# qi_pad.net
KiCad netlist of a schematic drawn in EAGLE
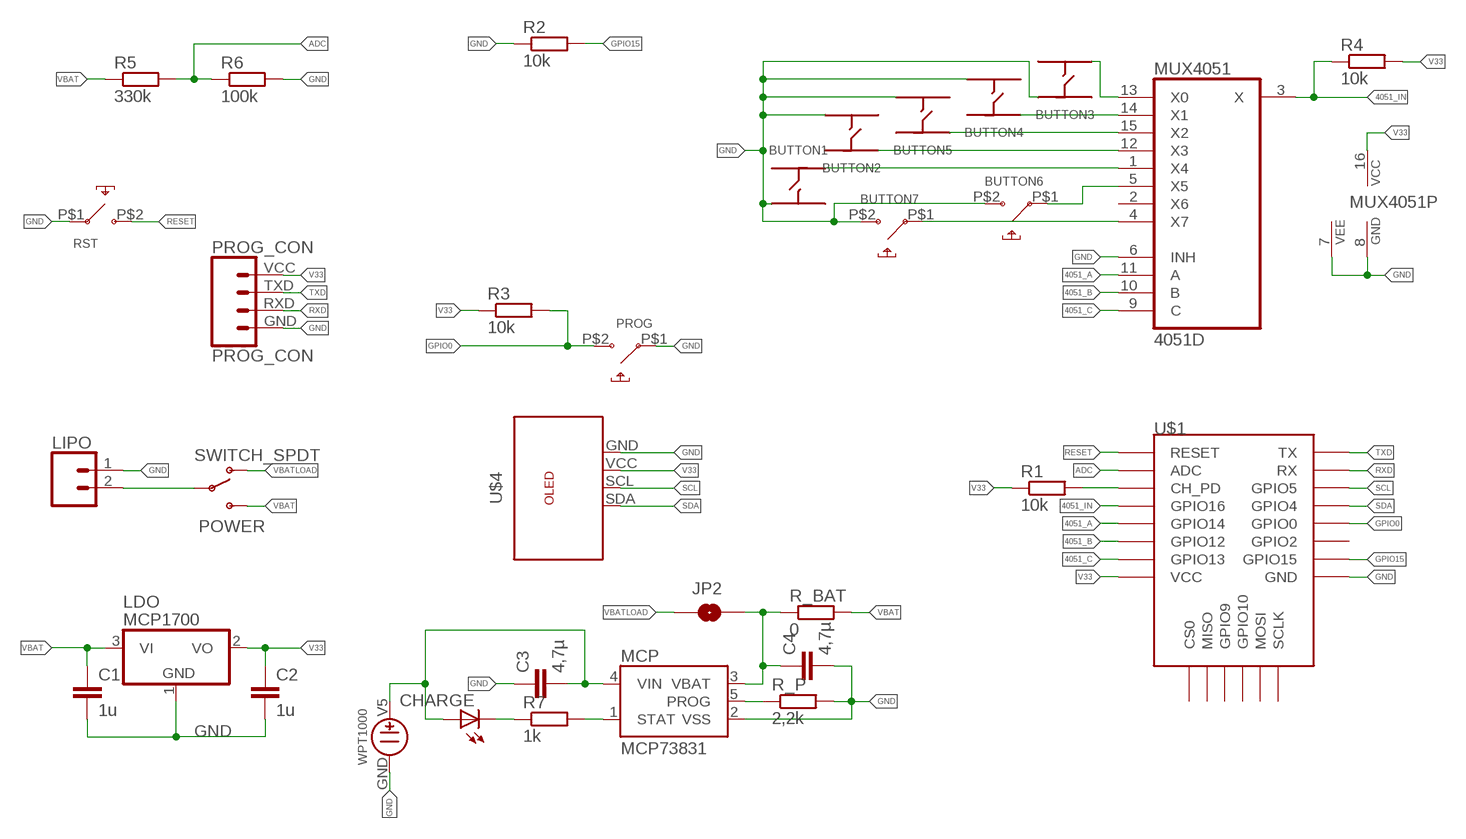
[diagram p0: schematic, sheet 1]

(export (version "E")
  (design (tool "Eeschema 10.0.6"))
  (components
    (comp (ref "BUTTON1")
      (value "6X6BUTTON")
      (footprint "eagle-import:6X6BUTTON")
      (libsource (lib "eagle-import") (part "6X6BUTTON"))
    )
    (comp (ref "BUTTON2")
      (value "6X6BUTTON")
      (footprint "eagle-import:6X6BUTTON")
      (libsource (lib "eagle-import") (part "6X6BUTTON"))
    )
    (comp (ref "BUTTON3")
      (value "6X6BUTTON")
      (footprint "eagle-import:6X6BUTTON")
      (libsource (lib "eagle-import") (part "6X6BUTTON"))
    )
    (comp (ref "BUTTON4")
      (value "6X6BUTTON")
      (footprint "eagle-import:6X6BUTTON")
      (libsource (lib "eagle-import") (part "6X6BUTTON"))
    )
    (comp (ref "BUTTON5")
      (value "6X6BUTTON")
      (footprint "eagle-import:6X6BUTTON")
      (libsource (lib "eagle-import") (part "6X6BUTTON"))
    )
    (comp (ref "BUTTON6")
      (value "3X4_SMD_BUTTON")
      (footprint "eagle-import:3X4BUTTON")
      (libsource (lib "eagle-import") (part "3X4_SMD_BUTTON"))
    )
    (comp (ref "BUTTON7")
      (value "3X4_SMD_BUTTON")
      (footprint "eagle-import:3X4BUTTON")
      (libsource (lib "eagle-import") (part "3X4_SMD_BUTTON"))
    )
    (comp (ref "C1")
      (value "1u")
      (footprint "eagle-import:C1206")
      (libsource (lib "eagle-import") (part "C-EUC1206"))
    )
    (comp (ref "C2")
      (value "1u")
      (footprint "eagle-import:C1206")
      (libsource (lib "eagle-import") (part "C-EUC1206"))
    )
    (comp (ref "C3")
      (value "4,7µ")
      (footprint "eagle-import:C1206")
      (libsource (lib "eagle-import") (part "C-EUC1206"))
    )
    (comp (ref "C4")
      (value "4,7µ")
      (footprint "eagle-import:C1206")
      (libsource (lib "eagle-import") (part "C-EUC1206"))
    )
    (comp (ref "CHARGE")
      (value "LEDCHIPLED_1206")
      (footprint "eagle-import:CHIPLED_1206")
      (libsource (lib "eagle-import") (part "LEDCHIPLED_1206"))
    )
    (comp (ref "JP2")
      (value "JUMPER-SMT_2_NO_NO-SILK")
      (footprint "eagle-import:SMT-JUMPER_2_NO_NO-SILK")
      (libsource (lib "eagle-import") (part "JUMPER-SMT_2_NO_NO-SILK"))
    )
    (comp (ref "LDO")
      (value "MCP1700")
      (footprint "eagle-import:SOT23")
      (libsource (lib "eagle-import") (part "MCP1703CB"))
    )
    (comp (ref "LIPO")
      (value "CONN_02-JST-2MM-SMT")
      (footprint "eagle-import:JST-2-SMD")
      (libsource (lib "eagle-import") (part "CONN_02-JST-2MM-SMT"))
    )
    (comp (ref "MCP")
      (value "MCP73831")
      (footprint "eagle-import:SOT23-5")
      (libsource (lib "eagle-import") (part "MCP73831"))
    )
    (comp (ref "MUX4051")
      (value "4051D")
      (footprint "eagle-import:SO16")
      (libsource (lib "eagle-import") (part "4051D"))
    )
    (comp (ref "POWER")
      (value "SWITCH_SPDT")
      (footprint "eagle-import:KPS-1290")
      (libsource (lib "eagle-import") (part "SWITCH_SPDT"))
    )
    (comp (ref "PROG")
      (value "3X6X3,5BUTTON90")
      (footprint "eagle-import:3X6X3,5BUTTON90")
      (libsource (lib "eagle-import") (part "3X6X3,5BUTTON90"))
    )
    (comp (ref "PROG_CON")
      (value "PROG_CON")
      (footprint "eagle-import:PROG_CON")
      (libsource (lib "eagle-import") (part "PROG_CON"))
    )
    (comp (ref "R1")
      (value "10k")
      (footprint "eagle-import:R0603")
      (libsource (lib "eagle-import") (part "R-EU_R0603"))
    )
    (comp (ref "R2")
      (value "10k")
      (footprint "eagle-import:R0603")
      (libsource (lib "eagle-import") (part "R-EU_R0603"))
    )
    (comp (ref "R3")
      (value "10k")
      (footprint "eagle-import:R0603")
      (libsource (lib "eagle-import") (part "R-EU_R0603"))
    )
    (comp (ref "R4")
      (value "10k")
      (footprint "eagle-import:R0603")
      (libsource (lib "eagle-import") (part "R-EU_R0603"))
    )
    (comp (ref "R5")
      (value "330k")
      (footprint "eagle-import:R0603")
      (libsource (lib "eagle-import") (part "R-EU_R0603"))
    )
    (comp (ref "R6")
      (value "100k")
      (footprint "eagle-import:R0603")
      (libsource (lib "eagle-import") (part "R-EU_R0603"))
    )
    (comp (ref "R7")
      (value "1k")
      (footprint "eagle-import:R0603")
      (libsource (lib "eagle-import") (part "R-EU_R0603"))
    )
    (comp (ref "RST")
      (value "3X6X3,5BUTTON90")
      (footprint "eagle-import:3X6X3,5BUTTON90")
      (libsource (lib "eagle-import") (part "3X6X3,5BUTTON90"))
    )
    (comp (ref "R_BAT")
      (value "0")
      (footprint "eagle-import:R1206")
      (libsource (lib "eagle-import") (part "R-EU_R1206"))
    )
    (comp (ref "R_P")
      (value "2,2k")
      (footprint "eagle-import:R0603")
      (libsource (lib "eagle-import") (part "R-EU_R0603"))
    )
    (comp (ref "U$1")
      (value "ESP8266-12F-SMD")
      (footprint "eagle-import:ESP8266-12F")
      (libsource (lib "eagle-import") (part "ESP8266-12F-SMD"))
    )
    (comp (ref "U$4")
      (value "OLED128X64")
      (footprint "eagle-import:OLED_128X64")
      (libsource (lib "eagle-import") (part "OLED128X64"))
    )
    (comp (ref "WPM1000")
      (value "WPT1000")
      (footprint "eagle-import:WPT1000")
      (libsource (lib "eagle-import") (part "WPT1000"))
    )
  )
  (nets
    (net (code "1") (name "4051_A") (class "Default")
      (node (ref "MUX4051") (pin "11") (pinfunction "A_11") (pintype "input"))
      (node (ref "U$1") (pin "GPIO14") (pinfunction "GPIO14_GPIO14") (pintype "bidirectional"))
    )
    (net (code "2") (name "4051_B") (class "Default")
      (node (ref "MUX4051") (pin "10") (pinfunction "B_10") (pintype "input"))
      (node (ref "U$1") (pin "GPIO12") (pinfunction "GPIO12_GPIO12") (pintype "bidirectional"))
    )
    (net (code "3") (name "4051_C") (class "Default")
      (node (ref "MUX4051") (pin "9") (pinfunction "C_9") (pintype "input"))
      (node (ref "U$1") (pin "GPIO13") (pinfunction "GPIO13_GPIO13") (pintype "bidirectional"))
    )
    (net (code "4") (name "4051_IN") (class "Default")
      (node (ref "MUX4051") (pin "3") (pinfunction "X_3") (pintype "bidirectional"))
      (node (ref "R4") (pin "1") (pinfunction "1_1") (pintype "passive"))
      (node (ref "U$1") (pin "GPIO16") (pinfunction "GPIO16_GPIO16") (pintype "bidirectional"))
    )
    (net (code "5") (name "ADC") (class "Default")
      (node (ref "R5") (pin "2") (pinfunction "2_2") (pintype "passive"))
      (node (ref "R6") (pin "1") (pinfunction "1_1") (pintype "passive"))
      (node (ref "U$1") (pin "ADC") (pinfunction "ADC_ADC") (pintype "bidirectional"))
    )
    (net (code "6") (name "GND") (class "Default")
      (node (ref "BUTTON1") (pin "P1") (pinfunction "A1_P1") (pintype "bidirectional"))
      (node (ref "BUTTON2") (pin "P2") (pinfunction "A2_P2") (pintype "bidirectional"))
      (node (ref "BUTTON3") (pin "P4") (pinfunction "U2_P4") (pintype "bidirectional"))
      (node (ref "BUTTON4") (pin "P2") (pinfunction "A2_P2") (pintype "bidirectional"))
      (node (ref "BUTTON5") (pin "P2") (pinfunction "A2_P2") (pintype "bidirectional"))
      (node (ref "BUTTON6") (pin "P$2") (pinfunction "P2_P$2") (pintype "bidirectional"))
      (node (ref "BUTTON7") (pin "P$2") (pinfunction "P2_P$2") (pintype "bidirectional"))
      (node (ref "C1") (pin "2") (pinfunction "2_2") (pintype "passive"))
      (node (ref "C2") (pin "2") (pinfunction "2_2") (pintype "passive"))
      (node (ref "C3") (pin "1") (pinfunction "1_1") (pintype "passive"))
      (node (ref "C4") (pin "2") (pinfunction "2_2") (pintype "passive"))
      (node (ref "LDO") (pin "1") (pinfunction "GND_1") (pintype "passive"))
      (node (ref "LIPO") (pin "1") (pinfunction "2_1") (pintype "passive"))
      (node (ref "MCP") (pin "2") (pinfunction "VSS_2") (pintype "power_in"))
      (node (ref "MUX4051") (pin "6") (pinfunction "INH_6") (pintype "input"))
      (node (ref "MUX4051") (pin "7") (pinfunction "VEE_7") (pintype "power_in"))
      (node (ref "MUX4051") (pin "8") (pinfunction "GND_8") (pintype "power_in"))
      (node (ref "PROG") (pin "P$1") (pinfunction "P1_P$1") (pintype "bidirectional"))
      (node (ref "PROG_CON") (pin "GND") (pinfunction "1_GND") (pintype "passive"))
      (node (ref "R2") (pin "1") (pinfunction "1_1") (pintype "passive"))
      (node (ref "R6") (pin "2") (pinfunction "2_2") (pintype "passive"))
      (node (ref "RST") (pin "P$1") (pinfunction "P1_P$1") (pintype "bidirectional"))
      (node (ref "R_P") (pin "2") (pinfunction "2_2") (pintype "passive"))
      (node (ref "U$1") (pin "GND") (pinfunction "GND_GND") (pintype "bidirectional"))
      (node (ref "U$4") (pin "GND") (pinfunction "GND_GND") (pintype "bidirectional"))
      (node (ref "WPM1000") (pin "GND") (pinfunction "GND_GND") (pintype "bidirectional"))
    )
    (net (code "7") (name "GPIO0") (class "Default")
      (node (ref "PROG") (pin "P$2") (pinfunction "P2_P$2") (pintype "bidirectional"))
      (node (ref "R3") (pin "2") (pinfunction "2_2") (pintype "passive"))
      (node (ref "U$1") (pin "GPIO0") (pinfunction "GPIO0_GPIO0") (pintype "bidirectional"))
    )
    (net (code "8") (name "GPIO15") (class "Default")
      (node (ref "R2") (pin "2") (pinfunction "2_2") (pintype "passive"))
      (node (ref "U$1") (pin "GPIO15") (pinfunction "GPIO15_GPIO15") (pintype "bidirectional"))
    )
    (net (code "9") (name "Net-(BUTTON1-U2)") (class "Default")
      (node (ref "BUTTON1") (pin "P4") (pinfunction "U2_P4") (pintype "bidirectional"))
      (node (ref "MUX4051") (pin "1") (pinfunction "X4_1") (pintype "bidirectional"))
    )
    (net (code "10") (name "Net-(BUTTON2-U1)") (class "Default")
      (node (ref "BUTTON2") (pin "P3") (pinfunction "U1_P3") (pintype "bidirectional"))
      (node (ref "MUX4051") (pin "12") (pinfunction "X3_12") (pintype "bidirectional"))
    )
    (net (code "11") (name "Net-(BUTTON3-A1)") (class "Default")
      (node (ref "BUTTON3") (pin "P1") (pinfunction "A1_P1") (pintype "bidirectional"))
      (node (ref "MUX4051") (pin "13") (pinfunction "X0_13") (pintype "bidirectional"))
    )
    (net (code "12") (name "Net-(BUTTON4-U1)") (class "Default")
      (node (ref "BUTTON4") (pin "P3") (pinfunction "U1_P3") (pintype "bidirectional"))
      (node (ref "MUX4051") (pin "14") (pinfunction "X1_14") (pintype "bidirectional"))
    )
    (net (code "13") (name "Net-(BUTTON5-U1)") (class "Default")
      (node (ref "BUTTON5") (pin "P3") (pinfunction "U1_P3") (pintype "bidirectional"))
      (node (ref "MUX4051") (pin "15") (pinfunction "X2_15") (pintype "bidirectional"))
    )
    (net (code "14") (name "Net-(BUTTON6-P1)") (class "Default")
      (node (ref "BUTTON6") (pin "P$1") (pinfunction "P1_P$1") (pintype "bidirectional"))
      (node (ref "MUX4051") (pin "5") (pinfunction "X5_5") (pintype "bidirectional"))
    )
    (net (code "15") (name "Net-(BUTTON7-P1)") (class "Default")
      (node (ref "BUTTON7") (pin "P$1") (pinfunction "P1_P$1") (pintype "bidirectional"))
      (node (ref "MUX4051") (pin "4") (pinfunction "X7_4") (pintype "bidirectional"))
    )
    (net (code "16") (name "Net-(CHARGE-PadC)") (class "Default")
      (node (ref "CHARGE") (pin "C") (pinfunction "C_C") (pintype "passive"))
      (node (ref "R7") (pin "1") (pinfunction "1_1") (pintype "passive"))
    )
    (net (code "17") (name "Net-(LIPO-1)") (class "Default")
      (node (ref "LIPO") (pin "2") (pinfunction "1_2") (pintype "passive"))
      (node (ref "POWER") (pin "P") (pinfunction "P_P") (pintype "passive"))
    )
    (net (code "18") (name "Net-(MCP-PROG)") (class "Default")
      (node (ref "MCP") (pin "5") (pinfunction "PROG_5") (pintype "input"))
      (node (ref "R_P") (pin "1") (pinfunction "1_1") (pintype "passive"))
    )
    (net (code "19") (name "Net-(MCP-STAT)") (class "Default")
      (node (ref "MCP") (pin "1") (pinfunction "STAT_1") (pintype "output"))
      (node (ref "R7") (pin "2") (pinfunction "2_2") (pintype "passive"))
    )
    (net (code "20") (name "Net-(MCP-VBAT)") (class "Default")
      (node (ref "C4") (pin "1") (pinfunction "1_1") (pintype "passive"))
      (node (ref "JP2") (pin "2") (pinfunction "2_2") (pintype "passive"))
      (node (ref "MCP") (pin "3") (pinfunction "VBAT_3") (pintype "power_in"))
      (node (ref "R_BAT") (pin "1") (pinfunction "1_1") (pintype "passive"))
    )
    (net (code "21") (name "Net-(MCP-VIN)") (class "Default")
      (node (ref "C3") (pin "2") (pinfunction "2_2") (pintype "passive"))
      (node (ref "CHARGE") (pin "A") (pinfunction "A_A") (pintype "passive"))
      (node (ref "MCP") (pin "4") (pinfunction "VIN_4") (pintype "power_in"))
      (node (ref "WPM1000") (pin "V5") (pinfunction "V5_V5") (pintype "bidirectional"))
    )
    (net (code "22") (name "Net-(U$1-CH_PD)") (class "Default")
      (node (ref "R1") (pin "2") (pinfunction "2_2") (pintype "passive"))
      (node (ref "U$1") (pin "EN") (pinfunction "CH_PD_EN") (pintype "bidirectional"))
    )
    (net (code "23") (name "RESET") (class "Default")
      (node (ref "RST") (pin "P$2") (pinfunction "P2_P$2") (pintype "bidirectional"))
      (node (ref "U$1") (pin "RESET") (pinfunction "RESET_RESET") (pintype "bidirectional"))
    )
    (net (code "24") (name "RXD") (class "Default")
      (node (ref "PROG_CON") (pin "RXD") (pinfunction "2_RXD") (pintype "passive"))
      (node (ref "U$1") (pin "RXD") (pinfunction "RX_RXD") (pintype "bidirectional"))
    )
    (net (code "25") (name "SCL") (class "Default")
      (node (ref "U$1") (pin "GPIO5") (pinfunction "GPIO5_GPIO5") (pintype "bidirectional"))
      (node (ref "U$4") (pin "SCL") (pinfunction "SCL_SCL") (pintype "bidirectional"))
    )
    (net (code "26") (name "SDA") (class "Default")
      (node (ref "U$1") (pin "GPIO4") (pinfunction "GPIO4_GPIO4") (pintype "bidirectional"))
      (node (ref "U$4") (pin "SDA") (pinfunction "SDA_SDA") (pintype "bidirectional"))
    )
    (net (code "27") (name "TXD") (class "Default")
      (node (ref "PROG_CON") (pin "TXD") (pinfunction "3_TXD") (pintype "passive"))
      (node (ref "U$1") (pin "TXD") (pinfunction "TX_TXD") (pintype "bidirectional"))
    )
    (net (code "28") (name "V33") (class "Default")
      (node (ref "C2") (pin "1") (pinfunction "1_1") (pintype "passive"))
      (node (ref "LDO") (pin "2") (pinfunction "VO_2") (pintype "passive"))
      (node (ref "MUX4051") (pin "16") (pinfunction "VCC_16") (pintype "power_in"))
      (node (ref "PROG_CON") (pin "VCC") (pinfunction "4_VCC") (pintype "passive"))
      (node (ref "R1") (pin "1") (pinfunction "1_1") (pintype "passive"))
      (node (ref "R3") (pin "1") (pinfunction "1_1") (pintype "passive"))
      (node (ref "R4") (pin "2") (pinfunction "2_2") (pintype "passive"))
      (node (ref "U$1") (pin "VCC") (pinfunction "VCC_VCC") (pintype "bidirectional"))
      (node (ref "U$4") (pin "VCC") (pinfunction "VCC_VCC") (pintype "bidirectional"))
    )
    (net (code "29") (name "VBAT") (class "Default")
      (node (ref "C1") (pin "1") (pinfunction "1_1") (pintype "passive"))
      (node (ref "LDO") (pin "3") (pinfunction "VI_3") (pintype "input"))
      (node (ref "POWER") (pin "S") (pinfunction "S_S") (pintype "passive"))
      (node (ref "R5") (pin "1") (pinfunction "1_1") (pintype "passive"))
      (node (ref "R_BAT") (pin "2") (pinfunction "2_2") (pintype "passive"))
    )
    (net (code "30") (name "VBATLOAD") (class "Default")
      (node (ref "JP2") (pin "1") (pinfunction "1_1") (pintype "passive"))
      (node (ref "POWER") (pin "O") (pinfunction "O_O") (pintype "passive"))
    )
    (net (code "31") (name "unconnected-(BUTTON1-A2-PadP2)") (class "Default")
      (node (ref "BUTTON1") (pin "P2") (pinfunction "A2_P2") (pintype "bidirectional"))
    )
    (net (code "32") (name "unconnected-(BUTTON1-U1-PadP3)") (class "Default")
      (node (ref "BUTTON1") (pin "P3") (pinfunction "U1_P3") (pintype "bidirectional"))
    )
    (net (code "33") (name "unconnected-(BUTTON2-A1-PadP1)") (class "Default")
      (node (ref "BUTTON2") (pin "P1") (pinfunction "A1_P1") (pintype "bidirectional"))
    )
    (net (code "34") (name "unconnected-(BUTTON2-U2-PadP4)") (class "Default")
      (node (ref "BUTTON2") (pin "P4") (pinfunction "U2_P4") (pintype "bidirectional"))
    )
    (net (code "35") (name "unconnected-(BUTTON3-A2-PadP2)") (class "Default")
      (node (ref "BUTTON3") (pin "P2") (pinfunction "A2_P2") (pintype "bidirectional"))
    )
    (net (code "36") (name "unconnected-(BUTTON3-U1-PadP3)") (class "Default")
      (node (ref "BUTTON3") (pin "P3") (pinfunction "U1_P3") (pintype "bidirectional"))
    )
    (net (code "37") (name "unconnected-(BUTTON4-A1-PadP1)") (class "Default")
      (node (ref "BUTTON4") (pin "P1") (pinfunction "A1_P1") (pintype "bidirectional"))
    )
    (net (code "38") (name "unconnected-(BUTTON4-U2-PadP4)") (class "Default")
      (node (ref "BUTTON4") (pin "P4") (pinfunction "U2_P4") (pintype "bidirectional"))
    )
    (net (code "39") (name "unconnected-(BUTTON5-A1-PadP1)") (class "Default")
      (node (ref "BUTTON5") (pin "P1") (pinfunction "A1_P1") (pintype "bidirectional"))
    )
    (net (code "40") (name "unconnected-(BUTTON5-U2-PadP4)") (class "Default")
      (node (ref "BUTTON5") (pin "P4") (pinfunction "U2_P4") (pintype "bidirectional"))
    )
    (net (code "41") (name "unconnected-(MUX4051A-X6-Pad2)") (class "Default")
      (node (ref "MUX4051") (pin "2") (pinfunction "X6_2") (pintype "bidirectional"))
    )
    (net (code "42") (name "unconnected-(U$1-PadCS0)") (class "Default")
      (node (ref "U$1") (pin "CS0") (pinfunction "CS0_CS0") (pintype "bidirectional"))
    )
    (net (code "43") (name "unconnected-(U$1-PadGPIO2)") (class "Default")
      (node (ref "U$1") (pin "GPIO2") (pinfunction "GPIO2_GPIO2") (pintype "bidirectional"))
    )
    (net (code "44") (name "unconnected-(U$1-PadGPIO9)") (class "Default")
      (node (ref "U$1") (pin "GPIO9") (pinfunction "GPIO9_GPIO9") (pintype "bidirectional"))
    )
    (net (code "45") (name "unconnected-(U$1-PadGPIO10)") (class "Default")
      (node (ref "U$1") (pin "GPIO10") (pinfunction "GPIO10_GPIO10") (pintype "bidirectional"))
    )
    (net (code "46") (name "unconnected-(U$1-PadMISO)") (class "Default")
      (node (ref "U$1") (pin "MISO") (pinfunction "MISO_MISO") (pintype "bidirectional"))
    )
    (net (code "47") (name "unconnected-(U$1-PadMOSI)") (class "Default")
      (node (ref "U$1") (pin "MOSI") (pinfunction "MOSI_MOSI") (pintype "bidirectional"))
    )
    (net (code "48") (name "unconnected-(U$1-PadSCLK)") (class "Default")
      (node (ref "U$1") (pin "SCLK") (pinfunction "SCLK_SCLK") (pintype "bidirectional"))
    )
  )
)
